# cdf-modular-bridge-rev2.net
KiCad netlist of a schematic drawn in EAGLE
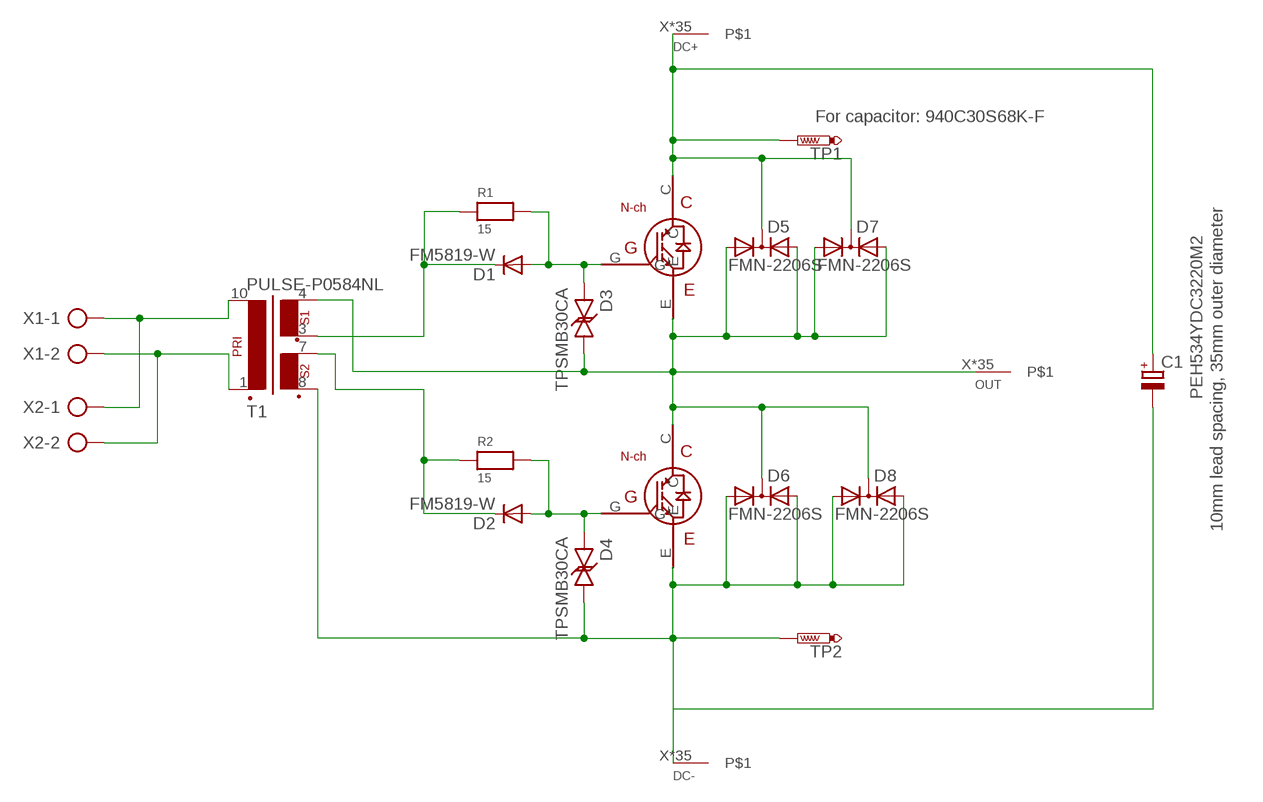
[diagram p0: schematic, sheet 1]

(export (version "E")
  (design (tool "Eeschema 10.0.6"))
  (components
    (comp (ref "C1")
      (value "PEH534YDC3220M2")
      (footprint "eagle-import:EB35D")
      (libsource (lib "eagle-import") (part "CPOL-EUE10-35"))
    )
    (comp (ref "D1")
      (value "FM5819-W")
      (footprint "eagle-import:DO214AC")
      (fields (field (name "MF") "Fairchild") (field (name "MPN") "S1A"))
      (libsource (lib "eagle-import") (part "S1A"))
    )
    (comp (ref "D2")
      (value "FM5819-W")
      (footprint "eagle-import:DO214AC")
      (fields (field (name "MF") "Fairchild") (field (name "MPN") "S1A"))
      (libsource (lib "eagle-import") (part "S1A"))
    )
    (comp (ref "D3")
      (value "TPSMB30CA")
      (footprint "eagle-import:TPSMB15CA")
      (libsource (lib "eagle-import") (part "TPSMB15CA"))
    )
    (comp (ref "D4")
      (value "TPSMB30CA")
      (footprint "eagle-import:TPSMB15CA")
      (libsource (lib "eagle-import") (part "TPSMB15CA"))
    )
    (comp (ref "D5")
      (value "FMN-2206S")
      (footprint "eagle-import:TO220ABS")
      (libsource (lib "eagle-import") (part "FMN-2206S"))
    )
    (comp (ref "D6")
      (value "FMN-2206S")
      (footprint "eagle-import:TO220ABS")
      (libsource (lib "eagle-import") (part "FMN-2206S"))
    )
    (comp (ref "D7")
      (value "FMN-2206S")
      (footprint "eagle-import:TO220ABS")
      (libsource (lib "eagle-import") (part "FMN-2206S"))
    )
    (comp (ref "D8")
      (value "FMN-2206S")
      (footprint "eagle-import:TO220ABS")
      (libsource (lib "eagle-import") (part "FMN-2206S"))
    )
    (comp (ref "DC+")
      (value "BIG-ASS-HOLE")
      (footprint "eagle-import:BIG-ASS-HOLE")
      (libsource (lib "eagle-import") (part "BIG-ASS-HOLE"))
    )
    (comp (ref "DC-")
      (value "BIG-ASS-HOLE")
      (footprint "eagle-import:BIG-ASS-HOLE")
      (libsource (lib "eagle-import") (part "BIG-ASS-HOLE"))
    )
    (comp (ref "OUT")
      (value "BIG-ASS-HOLE")
      (footprint "eagle-import:BIG-ASS-HOLE")
      (libsource (lib "eagle-import") (part "BIG-ASS-HOLE"))
    )
    (comp (ref "Q1")
      (value "Ixgh48n60a3")
      (footprint "eagle-import:IXGH40N60A")
      (libsource (lib "eagle-import") (part "IXGH40N60A"))
    )
    (comp (ref "Q2")
      (value "Ixgh48n60a3")
      (footprint "eagle-import:IXGH40N60A")
      (libsource (lib "eagle-import") (part "IXGH40N60A"))
    )
    (comp (ref "R1")
      (value "15")
      (footprint "eagle-import:1206")
      (libsource (lib "eagle-import") (part "RESISTOR1206"))
    )
    (comp (ref "R2")
      (value "15")
      (footprint "eagle-import:1206")
      (libsource (lib "eagle-import") (part "RESISTOR1206"))
    )
    (comp (ref "T1")
      (value "PULSE-P0584NL")
      (footprint "eagle-import:PULSE-P0584NL")
      (libsource (lib "eagle-import") (part "PULSE-P0584NL"))
    )
    (comp (ref "TP1")
      (value "PTR1PAD1-17")
      (footprint "eagle-import:P1-17")
      (libsource (lib "eagle-import") (part "PTR1PAD1-17"))
    )
    (comp (ref "TP2")
      (value "PTR1PAD1-17")
      (footprint "eagle-import:P1-17")
      (libsource (lib "eagle-import") (part "PTR1PAD1-17"))
    )
    (comp (ref "X1")
      (value "AK500/2")
      (footprint "eagle-import:AK500_2")
      (libsource (lib "eagle-import") (part "AK500/2"))
    )
    (comp (ref "X2")
      (value "AK500/2")
      (footprint "eagle-import:AK500_2")
      (libsource (lib "eagle-import") (part "AK500/2"))
    )
  )
  (nets
    (net (code "1") (name "Net-(C1-Pad+)") (class "Default")
      (node (ref "C1") (pin "+") (pinfunction "+_+") (pintype "passive"))
      (node (ref "D5") (pin "C") (pinfunction "C_C") (pintype "passive"))
      (node (ref "D7") (pin "C") (pinfunction "C_C") (pintype "passive"))
      (node (ref "DC+") (pin "X") (pinfunction "P$1_X") (pintype "bidirectional"))
      (node (ref "DC+") (pin "X@1") (pinfunction "P$1_X@1") (pintype "bidirectional"))
      (node (ref "DC+") (pin "X@10") (pinfunction "P$1_X@10") (pintype "bidirectional"))
      (node (ref "DC+") (pin "X@11") (pinfunction "P$1_X@11") (pintype "bidirectional"))
      (node (ref "DC+") (pin "X@12") (pinfunction "P$1_X@12") (pintype "bidirectional"))
      (node (ref "DC+") (pin "X@120") (pinfunction "P$1_X@120") (pintype "bidirectional"))
      (node (ref "DC+") (pin "X@13") (pinfunction "P$1_X@13") (pintype "bidirectional"))
      (node (ref "DC+") (pin "X@14") (pinfunction "P$1_X@14") (pintype "bidirectional"))
      (node (ref "DC+") (pin "X@15") (pinfunction "P$1_X@15") (pintype "bidirectional"))
      (node (ref "DC+") (pin "X@16") (pinfunction "P$1_X@16") (pintype "bidirectional"))
      (node (ref "DC+") (pin "X@17") (pinfunction "P$1_X@17") (pintype "bidirectional"))
      (node (ref "DC+") (pin "X@18") (pinfunction "P$1_X@18") (pintype "bidirectional"))
      (node (ref "DC+") (pin "X@19") (pinfunction "P$1_X@19") (pintype "bidirectional"))
      (node (ref "DC+") (pin "X@2") (pinfunction "P$1_X@2") (pintype "bidirectional"))
      (node (ref "DC+") (pin "X@20") (pinfunction "P$1_X@20") (pintype "bidirectional"))
      (node (ref "DC+") (pin "X@21") (pinfunction "P$1_X@21") (pintype "bidirectional"))
      (node (ref "DC+") (pin "X@22") (pinfunction "P$1_X@22") (pintype "bidirectional"))
      (node (ref "DC+") (pin "X@23") (pinfunction "P$1_X@23") (pintype "bidirectional"))
      (node (ref "DC+") (pin "X@24") (pinfunction "P$1_X@24") (pintype "bidirectional"))
      (node (ref "DC+") (pin "X@25") (pinfunction "P$1_X@25") (pintype "bidirectional"))
      (node (ref "DC+") (pin "X@26") (pinfunction "P$1_X@26") (pintype "bidirectional"))
      (node (ref "DC+") (pin "X@27") (pinfunction "P$1_X@27") (pintype "bidirectional"))
      (node (ref "DC+") (pin "X@28") (pinfunction "P$1_X@28") (pintype "bidirectional"))
      (node (ref "DC+") (pin "X@29") (pinfunction "P$1_X@29") (pintype "bidirectional"))
      (node (ref "DC+") (pin "X@3") (pinfunction "P$1_X@3") (pintype "bidirectional"))
      (node (ref "DC+") (pin "X@30") (pinfunction "P$1_X@30") (pintype "bidirectional"))
      (node (ref "DC+") (pin "X@31") (pinfunction "P$1_X@31") (pintype "bidirectional"))
      (node (ref "DC+") (pin "X@32") (pinfunction "P$1_X@32") (pintype "bidirectional"))
      (node (ref "DC+") (pin "X@34") (pinfunction "P$1_X@34") (pintype "bidirectional"))
      (node (ref "DC+") (pin "X@4") (pinfunction "P$1_X@4") (pintype "bidirectional"))
      (node (ref "DC+") (pin "X@5") (pinfunction "P$1_X@5") (pintype "bidirectional"))
      (node (ref "DC+") (pin "X@6") (pinfunction "P$1_X@6") (pintype "bidirectional"))
      (node (ref "DC+") (pin "X@7") (pinfunction "P$1_X@7") (pintype "bidirectional"))
      (node (ref "DC+") (pin "X@8") (pinfunction "P$1_X@8") (pintype "bidirectional"))
      (node (ref "DC+") (pin "X@9") (pinfunction "P$1_X@9") (pintype "bidirectional"))
      (node (ref "Q1") (pin "C") (pinfunction "C_C") (pintype "bidirectional"))
      (node (ref "TP1") (pin "TP") (pinfunction "TP_TP") (pintype "input"))
    )
    (net (code "2") (name "Net-(D1-PadA)") (class "Default")
      (node (ref "D1") (pin "A") (pinfunction "A_A") (pintype "passive"))
      (node (ref "D3") (pin "P$1") (pinfunction "P$1_P$1") (pintype "passive"))
      (node (ref "Q1") (pin "G") (pinfunction "G_G") (pintype "bidirectional"))
      (node (ref "R1") (pin "2") (pinfunction "2_2") (pintype "passive"))
    )
    (net (code "3") (name "Net-(D2-PadA)") (class "Default")
      (node (ref "D2") (pin "A") (pinfunction "A_A") (pintype "passive"))
      (node (ref "D4") (pin "P$1") (pinfunction "P$1_P$1") (pintype "passive"))
      (node (ref "Q2") (pin "G") (pinfunction "G_G") (pintype "bidirectional"))
      (node (ref "R2") (pin "2") (pinfunction "2_2") (pintype "passive"))
    )
    (net (code "4") (name "Net-(T1-PRI_NEG)") (class "Default")
      (node (ref "T1") (pin "10") (pinfunction "PRI_NEG_10") (pintype "passive"))
      (node (ref "X1") (pin "1") (pinfunction "KL_1") (pintype "passive"))
      (node (ref "X2") (pin "1") (pinfunction "KL_1") (pintype "passive"))
    )
    (net (code "5") (name "Net-(T1-PRI_POS)") (class "Default")
      (node (ref "T1") (pin "1") (pinfunction "PRI_POS_1") (pintype "passive"))
      (node (ref "X1") (pin "2") (pinfunction "KL_2") (pintype "passive"))
      (node (ref "X2") (pin "2") (pinfunction "KL_2") (pintype "passive"))
    )
    (net (code "6") (name "Net-(T1-SEC1_NEG)") (class "Default")
      (node (ref "D3") (pin "P$2") (pinfunction "P$2_P$2") (pintype "passive"))
      (node (ref "D5") (pin "A1") (pinfunction "A1_A1") (pintype "passive"))
      (node (ref "D5") (pin "A2") (pinfunction "A2_A2") (pintype "passive"))
      (node (ref "D6") (pin "C") (pinfunction "C_C") (pintype "passive"))
      (node (ref "D7") (pin "A1") (pinfunction "A1_A1") (pintype "passive"))
      (node (ref "D7") (pin "A2") (pinfunction "A2_A2") (pintype "passive"))
      (node (ref "D8") (pin "C") (pinfunction "C_C") (pintype "passive"))
      (node (ref "OUT") (pin "X") (pinfunction "P$1_X") (pintype "bidirectional"))
      (node (ref "OUT") (pin "X@1") (pinfunction "P$1_X@1") (pintype "bidirectional"))
      (node (ref "OUT") (pin "X@10") (pinfunction "P$1_X@10") (pintype "bidirectional"))
      (node (ref "OUT") (pin "X@11") (pinfunction "P$1_X@11") (pintype "bidirectional"))
      (node (ref "OUT") (pin "X@12") (pinfunction "P$1_X@12") (pintype "bidirectional"))
      (node (ref "OUT") (pin "X@120") (pinfunction "P$1_X@120") (pintype "bidirectional"))
      (node (ref "OUT") (pin "X@13") (pinfunction "P$1_X@13") (pintype "bidirectional"))
      (node (ref "OUT") (pin "X@14") (pinfunction "P$1_X@14") (pintype "bidirectional"))
      (node (ref "OUT") (pin "X@15") (pinfunction "P$1_X@15") (pintype "bidirectional"))
      (node (ref "OUT") (pin "X@16") (pinfunction "P$1_X@16") (pintype "bidirectional"))
      (node (ref "OUT") (pin "X@17") (pinfunction "P$1_X@17") (pintype "bidirectional"))
      (node (ref "OUT") (pin "X@18") (pinfunction "P$1_X@18") (pintype "bidirectional"))
      (node (ref "OUT") (pin "X@19") (pinfunction "P$1_X@19") (pintype "bidirectional"))
      (node (ref "OUT") (pin "X@2") (pinfunction "P$1_X@2") (pintype "bidirectional"))
      (node (ref "OUT") (pin "X@20") (pinfunction "P$1_X@20") (pintype "bidirectional"))
      (node (ref "OUT") (pin "X@21") (pinfunction "P$1_X@21") (pintype "bidirectional"))
      (node (ref "OUT") (pin "X@22") (pinfunction "P$1_X@22") (pintype "bidirectional"))
      (node (ref "OUT") (pin "X@23") (pinfunction "P$1_X@23") (pintype "bidirectional"))
      (node (ref "OUT") (pin "X@24") (pinfunction "P$1_X@24") (pintype "bidirectional"))
      (node (ref "OUT") (pin "X@25") (pinfunction "P$1_X@25") (pintype "bidirectional"))
      (node (ref "OUT") (pin "X@26") (pinfunction "P$1_X@26") (pintype "bidirectional"))
      (node (ref "OUT") (pin "X@27") (pinfunction "P$1_X@27") (pintype "bidirectional"))
      (node (ref "OUT") (pin "X@28") (pinfunction "P$1_X@28") (pintype "bidirectional"))
      (node (ref "OUT") (pin "X@29") (pinfunction "P$1_X@29") (pintype "bidirectional"))
      (node (ref "OUT") (pin "X@3") (pinfunction "P$1_X@3") (pintype "bidirectional"))
      (node (ref "OUT") (pin "X@30") (pinfunction "P$1_X@30") (pintype "bidirectional"))
      (node (ref "OUT") (pin "X@31") (pinfunction "P$1_X@31") (pintype "bidirectional"))
      (node (ref "OUT") (pin "X@32") (pinfunction "P$1_X@32") (pintype "bidirectional"))
      (node (ref "OUT") (pin "X@34") (pinfunction "P$1_X@34") (pintype "bidirectional"))
      (node (ref "OUT") (pin "X@4") (pinfunction "P$1_X@4") (pintype "bidirectional"))
      (node (ref "OUT") (pin "X@5") (pinfunction "P$1_X@5") (pintype "bidirectional"))
      (node (ref "OUT") (pin "X@6") (pinfunction "P$1_X@6") (pintype "bidirectional"))
      (node (ref "OUT") (pin "X@7") (pinfunction "P$1_X@7") (pintype "bidirectional"))
      (node (ref "OUT") (pin "X@8") (pinfunction "P$1_X@8") (pintype "bidirectional"))
      (node (ref "OUT") (pin "X@9") (pinfunction "P$1_X@9") (pintype "bidirectional"))
      (node (ref "Q1") (pin "E") (pinfunction "E_E") (pintype "bidirectional"))
      (node (ref "Q2") (pin "C") (pinfunction "C_C") (pintype "bidirectional"))
      (node (ref "T1") (pin "4") (pinfunction "SEC1_NEG_4") (pintype "passive"))
    )
    (net (code "7") (name "Net-(T1-SEC1_POS)") (class "Default")
      (node (ref "D1") (pin "C") (pinfunction "C_C") (pintype "passive"))
      (node (ref "R1") (pin "1") (pinfunction "1_1") (pintype "passive"))
      (node (ref "T1") (pin "3") (pinfunction "SEC1_POS_3") (pintype "passive"))
    )
    (net (code "8") (name "Net-(T1-SEC2_NEG)") (class "Default")
      (node (ref "D2") (pin "C") (pinfunction "C_C") (pintype "passive"))
      (node (ref "R2") (pin "1") (pinfunction "1_1") (pintype "passive"))
      (node (ref "T1") (pin "7") (pinfunction "SEC2_NEG_7") (pintype "passive"))
    )
    (net (code "9") (name "Net-(T1-SEC2_POS)") (class "Default")
      (node (ref "C1") (pin "-") (pinfunction "-_-") (pintype "passive"))
      (node (ref "D4") (pin "P$2") (pinfunction "P$2_P$2") (pintype "passive"))
      (node (ref "D6") (pin "A1") (pinfunction "A1_A1") (pintype "passive"))
      (node (ref "D6") (pin "A2") (pinfunction "A2_A2") (pintype "passive"))
      (node (ref "D8") (pin "A1") (pinfunction "A1_A1") (pintype "passive"))
      (node (ref "D8") (pin "A2") (pinfunction "A2_A2") (pintype "passive"))
      (node (ref "DC-") (pin "X") (pinfunction "P$1_X") (pintype "bidirectional"))
      (node (ref "DC-") (pin "X@1") (pinfunction "P$1_X@1") (pintype "bidirectional"))
      (node (ref "DC-") (pin "X@10") (pinfunction "P$1_X@10") (pintype "bidirectional"))
      (node (ref "DC-") (pin "X@11") (pinfunction "P$1_X@11") (pintype "bidirectional"))
      (node (ref "DC-") (pin "X@12") (pinfunction "P$1_X@12") (pintype "bidirectional"))
      (node (ref "DC-") (pin "X@120") (pinfunction "P$1_X@120") (pintype "bidirectional"))
      (node (ref "DC-") (pin "X@13") (pinfunction "P$1_X@13") (pintype "bidirectional"))
      (node (ref "DC-") (pin "X@14") (pinfunction "P$1_X@14") (pintype "bidirectional"))
      (node (ref "DC-") (pin "X@15") (pinfunction "P$1_X@15") (pintype "bidirectional"))
      (node (ref "DC-") (pin "X@16") (pinfunction "P$1_X@16") (pintype "bidirectional"))
      (node (ref "DC-") (pin "X@17") (pinfunction "P$1_X@17") (pintype "bidirectional"))
      (node (ref "DC-") (pin "X@18") (pinfunction "P$1_X@18") (pintype "bidirectional"))
      (node (ref "DC-") (pin "X@19") (pinfunction "P$1_X@19") (pintype "bidirectional"))
      (node (ref "DC-") (pin "X@2") (pinfunction "P$1_X@2") (pintype "bidirectional"))
      (node (ref "DC-") (pin "X@20") (pinfunction "P$1_X@20") (pintype "bidirectional"))
      (node (ref "DC-") (pin "X@21") (pinfunction "P$1_X@21") (pintype "bidirectional"))
      (node (ref "DC-") (pin "X@22") (pinfunction "P$1_X@22") (pintype "bidirectional"))
      (node (ref "DC-") (pin "X@23") (pinfunction "P$1_X@23") (pintype "bidirectional"))
      (node (ref "DC-") (pin "X@24") (pinfunction "P$1_X@24") (pintype "bidirectional"))
      (node (ref "DC-") (pin "X@25") (pinfunction "P$1_X@25") (pintype "bidirectional"))
      (node (ref "DC-") (pin "X@26") (pinfunction "P$1_X@26") (pintype "bidirectional"))
      (node (ref "DC-") (pin "X@27") (pinfunction "P$1_X@27") (pintype "bidirectional"))
      (node (ref "DC-") (pin "X@28") (pinfunction "P$1_X@28") (pintype "bidirectional"))
      (node (ref "DC-") (pin "X@29") (pinfunction "P$1_X@29") (pintype "bidirectional"))
      (node (ref "DC-") (pin "X@3") (pinfunction "P$1_X@3") (pintype "bidirectional"))
      (node (ref "DC-") (pin "X@30") (pinfunction "P$1_X@30") (pintype "bidirectional"))
      (node (ref "DC-") (pin "X@31") (pinfunction "P$1_X@31") (pintype "bidirectional"))
      (node (ref "DC-") (pin "X@32") (pinfunction "P$1_X@32") (pintype "bidirectional"))
      (node (ref "DC-") (pin "X@34") (pinfunction "P$1_X@34") (pintype "bidirectional"))
      (node (ref "DC-") (pin "X@4") (pinfunction "P$1_X@4") (pintype "bidirectional"))
      (node (ref "DC-") (pin "X@5") (pinfunction "P$1_X@5") (pintype "bidirectional"))
      (node (ref "DC-") (pin "X@6") (pinfunction "P$1_X@6") (pintype "bidirectional"))
      (node (ref "DC-") (pin "X@7") (pinfunction "P$1_X@7") (pintype "bidirectional"))
      (node (ref "DC-") (pin "X@8") (pinfunction "P$1_X@8") (pintype "bidirectional"))
      (node (ref "DC-") (pin "X@9") (pinfunction "P$1_X@9") (pintype "bidirectional"))
      (node (ref "Q2") (pin "E") (pinfunction "E_E") (pintype "bidirectional"))
      (node (ref "T1") (pin "8") (pinfunction "SEC2_POS_8") (pintype "passive"))
      (node (ref "TP2") (pin "TP") (pinfunction "TP_TP") (pintype "input"))
    )
  )
)
